# UART_matrix_v0_2.net
KiCad netlist of a schematic drawn in EAGLE
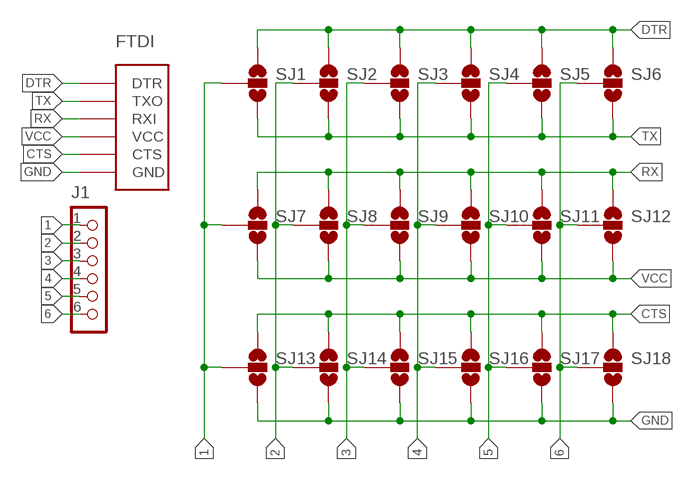
[diagram p0: schematic, sheet 1]

(export (version "E")
  (design (tool "Eeschema 10.0.6"))
  (components
    (comp (ref "FTDI")
      (value "FTDI_DEVICE")
      (footprint "eagle-import:FTDI_DEVICE_SIDE")
      (libsource (lib "eagle-import") (part "FTDI_DEVICE"))
    )
    (comp (ref "J1")
      (value "CON_HEADER_1X06-PTH")
      (footprint "eagle-import:M1X6")
      (libsource (lib "eagle-import") (part "CON_HEADER_1X06-PTH"))
    )
    (comp (ref "SJ1")
      (value "SOLDERJUMPER_2WAYT")
      (footprint "eagle-import:SJ_2")
      (libsource (lib "eagle-import") (part "SOLDERJUMPER_2WAYT"))
    )
    (comp (ref "SJ2")
      (value "SOLDERJUMPER_2WAYT")
      (footprint "eagle-import:SJ_2")
      (libsource (lib "eagle-import") (part "SOLDERJUMPER_2WAYT"))
    )
    (comp (ref "SJ3")
      (value "SOLDERJUMPER_2WAYT")
      (footprint "eagle-import:SJ_2")
      (libsource (lib "eagle-import") (part "SOLDERJUMPER_2WAYT"))
    )
    (comp (ref "SJ4")
      (value "SOLDERJUMPER_2WAYT")
      (footprint "eagle-import:SJ_2")
      (libsource (lib "eagle-import") (part "SOLDERJUMPER_2WAYT"))
    )
    (comp (ref "SJ5")
      (value "SOLDERJUMPER_2WAYT")
      (footprint "eagle-import:SJ_2")
      (libsource (lib "eagle-import") (part "SOLDERJUMPER_2WAYT"))
    )
    (comp (ref "SJ6")
      (value "SOLDERJUMPER_2WAYT")
      (footprint "eagle-import:SJ_2")
      (libsource (lib "eagle-import") (part "SOLDERJUMPER_2WAYT"))
    )
    (comp (ref "SJ7")
      (value "SOLDERJUMPER_2WAYT")
      (footprint "eagle-import:SJ_2")
      (libsource (lib "eagle-import") (part "SOLDERJUMPER_2WAYT"))
    )
    (comp (ref "SJ8")
      (value "SOLDERJUMPER_2WAYT")
      (footprint "eagle-import:SJ_2")
      (libsource (lib "eagle-import") (part "SOLDERJUMPER_2WAYT"))
    )
    (comp (ref "SJ9")
      (value "SOLDERJUMPER_2WAYT")
      (footprint "eagle-import:SJ_2")
      (libsource (lib "eagle-import") (part "SOLDERJUMPER_2WAYT"))
    )
    (comp (ref "SJ10")
      (value "SOLDERJUMPER_2WAYT")
      (footprint "eagle-import:SJ_2")
      (libsource (lib "eagle-import") (part "SOLDERJUMPER_2WAYT"))
    )
    (comp (ref "SJ11")
      (value "SOLDERJUMPER_2WAYT")
      (footprint "eagle-import:SJ_2")
      (libsource (lib "eagle-import") (part "SOLDERJUMPER_2WAYT"))
    )
    (comp (ref "SJ12")
      (value "SOLDERJUMPER_2WAYT")
      (footprint "eagle-import:SJ_2")
      (libsource (lib "eagle-import") (part "SOLDERJUMPER_2WAYT"))
    )
    (comp (ref "SJ13")
      (value "SOLDERJUMPER_2WAYT")
      (footprint "eagle-import:SJ_2")
      (libsource (lib "eagle-import") (part "SOLDERJUMPER_2WAYT"))
    )
    (comp (ref "SJ14")
      (value "SOLDERJUMPER_2WAYT")
      (footprint "eagle-import:SJ_2")
      (libsource (lib "eagle-import") (part "SOLDERJUMPER_2WAYT"))
    )
    (comp (ref "SJ15")
      (value "SOLDERJUMPER_2WAYT")
      (footprint "eagle-import:SJ_2")
      (libsource (lib "eagle-import") (part "SOLDERJUMPER_2WAYT"))
    )
    (comp (ref "SJ16")
      (value "SOLDERJUMPER_2WAYT")
      (footprint "eagle-import:SJ_2")
      (libsource (lib "eagle-import") (part "SOLDERJUMPER_2WAYT"))
    )
    (comp (ref "SJ17")
      (value "SOLDERJUMPER_2WAYT")
      (footprint "eagle-import:SJ_2")
      (libsource (lib "eagle-import") (part "SOLDERJUMPER_2WAYT"))
    )
    (comp (ref "SJ18")
      (value "SOLDERJUMPER_2WAYT")
      (footprint "eagle-import:SJ_2")
      (libsource (lib "eagle-import") (part "SOLDERJUMPER_2WAYT"))
    )
  )
  (nets
    (net (code "1") (name "1") (class "Default")
      (node (ref "J1") (pin "1") (pinfunction "1_1") (pintype "bidirectional"))
      (node (ref "SJ1") (pin "2") (pinfunction "2_2") (pintype "passive"))
      (node (ref "SJ13") (pin "2") (pinfunction "2_2") (pintype "passive"))
      (node (ref "SJ7") (pin "2") (pinfunction "2_2") (pintype "passive"))
    )
    (net (code "2") (name "2") (class "Default")
      (node (ref "J1") (pin "2") (pinfunction "2_2") (pintype "bidirectional"))
      (node (ref "SJ14") (pin "2") (pinfunction "2_2") (pintype "passive"))
      (node (ref "SJ2") (pin "2") (pinfunction "2_2") (pintype "passive"))
      (node (ref "SJ8") (pin "2") (pinfunction "2_2") (pintype "passive"))
    )
    (net (code "3") (name "3") (class "Default")
      (node (ref "J1") (pin "3") (pinfunction "3_3") (pintype "passive"))
      (node (ref "SJ15") (pin "2") (pinfunction "2_2") (pintype "passive"))
      (node (ref "SJ3") (pin "2") (pinfunction "2_2") (pintype "passive"))
      (node (ref "SJ9") (pin "2") (pinfunction "2_2") (pintype "passive"))
    )
    (net (code "4") (name "4") (class "Default")
      (node (ref "J1") (pin "4") (pinfunction "4_4") (pintype "passive"))
      (node (ref "SJ10") (pin "2") (pinfunction "2_2") (pintype "passive"))
      (node (ref "SJ16") (pin "2") (pinfunction "2_2") (pintype "passive"))
      (node (ref "SJ4") (pin "2") (pinfunction "2_2") (pintype "passive"))
    )
    (net (code "5") (name "5") (class "Default")
      (node (ref "J1") (pin "5") (pinfunction "5_5") (pintype "passive"))
      (node (ref "SJ11") (pin "2") (pinfunction "2_2") (pintype "passive"))
      (node (ref "SJ17") (pin "2") (pinfunction "2_2") (pintype "passive"))
      (node (ref "SJ5") (pin "2") (pinfunction "2_2") (pintype "passive"))
    )
    (net (code "6") (name "6") (class "Default")
      (node (ref "J1") (pin "6") (pinfunction "6_6") (pintype "passive"))
      (node (ref "SJ12") (pin "2") (pinfunction "2_2") (pintype "passive"))
      (node (ref "SJ18") (pin "2") (pinfunction "2_2") (pintype "passive"))
      (node (ref "SJ6") (pin "2") (pinfunction "2_2") (pintype "passive"))
    )
    (net (code "7") (name "CTS") (class "Default")
      (node (ref "FTDI") (pin "P$5") (pinfunction "CTS_P$5") (pintype "bidirectional"))
      (node (ref "SJ13") (pin "1") (pinfunction "1_1") (pintype "passive"))
      (node (ref "SJ14") (pin "1") (pinfunction "1_1") (pintype "passive"))
      (node (ref "SJ15") (pin "1") (pinfunction "1_1") (pintype "passive"))
      (node (ref "SJ16") (pin "1") (pinfunction "1_1") (pintype "passive"))
      (node (ref "SJ17") (pin "1") (pinfunction "1_1") (pintype "passive"))
      (node (ref "SJ18") (pin "1") (pinfunction "1_1") (pintype "passive"))
    )
    (net (code "8") (name "DTR") (class "Default")
      (node (ref "FTDI") (pin "P$1") (pinfunction "DTR_P$1") (pintype "bidirectional"))
      (node (ref "SJ1") (pin "1") (pinfunction "1_1") (pintype "passive"))
      (node (ref "SJ2") (pin "1") (pinfunction "1_1") (pintype "passive"))
      (node (ref "SJ3") (pin "1") (pinfunction "1_1") (pintype "passive"))
      (node (ref "SJ4") (pin "1") (pinfunction "1_1") (pintype "passive"))
      (node (ref "SJ5") (pin "1") (pinfunction "1_1") (pintype "passive"))
      (node (ref "SJ6") (pin "1") (pinfunction "1_1") (pintype "passive"))
    )
    (net (code "9") (name "GND") (class "Default")
      (node (ref "FTDI") (pin "P$6") (pinfunction "GND_P$6") (pintype "bidirectional"))
      (node (ref "SJ13") (pin "3") (pinfunction "3_3") (pintype "passive"))
      (node (ref "SJ14") (pin "3") (pinfunction "3_3") (pintype "passive"))
      (node (ref "SJ15") (pin "3") (pinfunction "3_3") (pintype "passive"))
      (node (ref "SJ16") (pin "3") (pinfunction "3_3") (pintype "passive"))
      (node (ref "SJ17") (pin "3") (pinfunction "3_3") (pintype "passive"))
      (node (ref "SJ18") (pin "3") (pinfunction "3_3") (pintype "passive"))
    )
    (net (code "10") (name "RX") (class "Default")
      (node (ref "FTDI") (pin "P$3") (pinfunction "RXI_P$3") (pintype "bidirectional"))
      (node (ref "SJ10") (pin "1") (pinfunction "1_1") (pintype "passive"))
      (node (ref "SJ11") (pin "1") (pinfunction "1_1") (pintype "passive"))
      (node (ref "SJ12") (pin "1") (pinfunction "1_1") (pintype "passive"))
      (node (ref "SJ7") (pin "1") (pinfunction "1_1") (pintype "passive"))
      (node (ref "SJ8") (pin "1") (pinfunction "1_1") (pintype "passive"))
      (node (ref "SJ9") (pin "1") (pinfunction "1_1") (pintype "passive"))
    )
    (net (code "11") (name "TX") (class "Default")
      (node (ref "FTDI") (pin "P$2") (pinfunction "TXO_P$2") (pintype "bidirectional"))
      (node (ref "SJ1") (pin "3") (pinfunction "3_3") (pintype "passive"))
      (node (ref "SJ2") (pin "3") (pinfunction "3_3") (pintype "passive"))
      (node (ref "SJ3") (pin "3") (pinfunction "3_3") (pintype "passive"))
      (node (ref "SJ4") (pin "3") (pinfunction "3_3") (pintype "passive"))
      (node (ref "SJ5") (pin "3") (pinfunction "3_3") (pintype "passive"))
      (node (ref "SJ6") (pin "3") (pinfunction "3_3") (pintype "passive"))
    )
    (net (code "12") (name "VCC") (class "Default")
      (node (ref "FTDI") (pin "P$4") (pinfunction "VCC_P$4") (pintype "bidirectional"))
      (node (ref "SJ10") (pin "3") (pinfunction "3_3") (pintype "passive"))
      (node (ref "SJ11") (pin "3") (pinfunction "3_3") (pintype "passive"))
      (node (ref "SJ12") (pin "3") (pinfunction "3_3") (pintype "passive"))
      (node (ref "SJ7") (pin "3") (pinfunction "3_3") (pintype "passive"))
      (node (ref "SJ8") (pin "3") (pinfunction "3_3") (pintype "passive"))
      (node (ref "SJ9") (pin "3") (pinfunction "3_3") (pintype "passive"))
    )
  )
)
